# PhotonHome.net
KiCad netlist of a schematic drawn in EAGLE
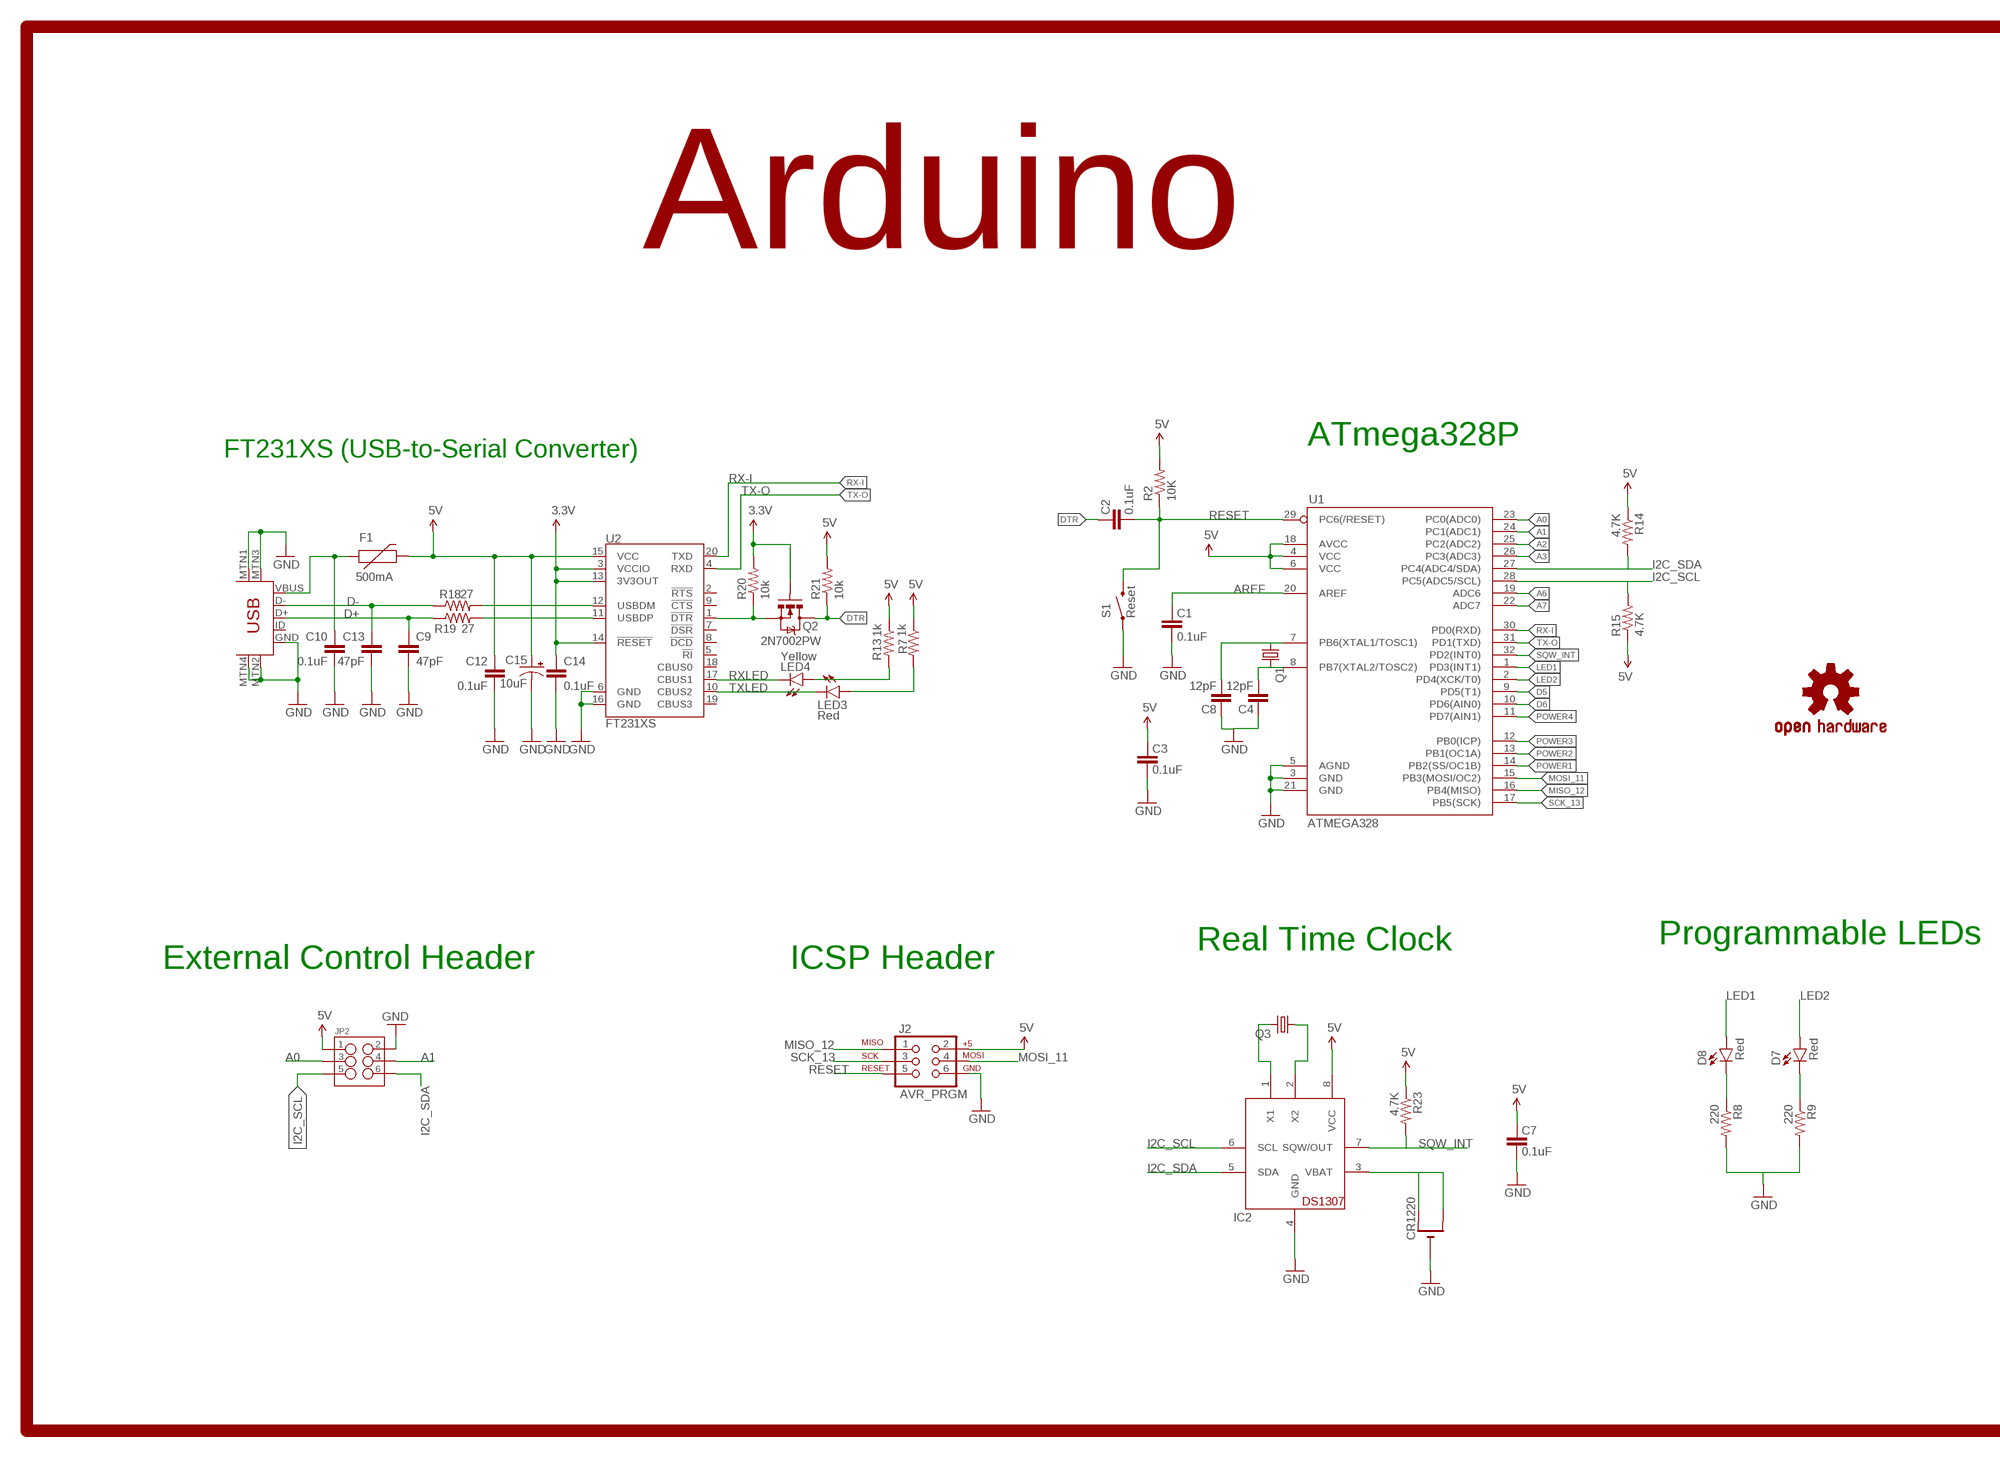
[diagram p0: schematic, sheet 1, part 1 of 2]
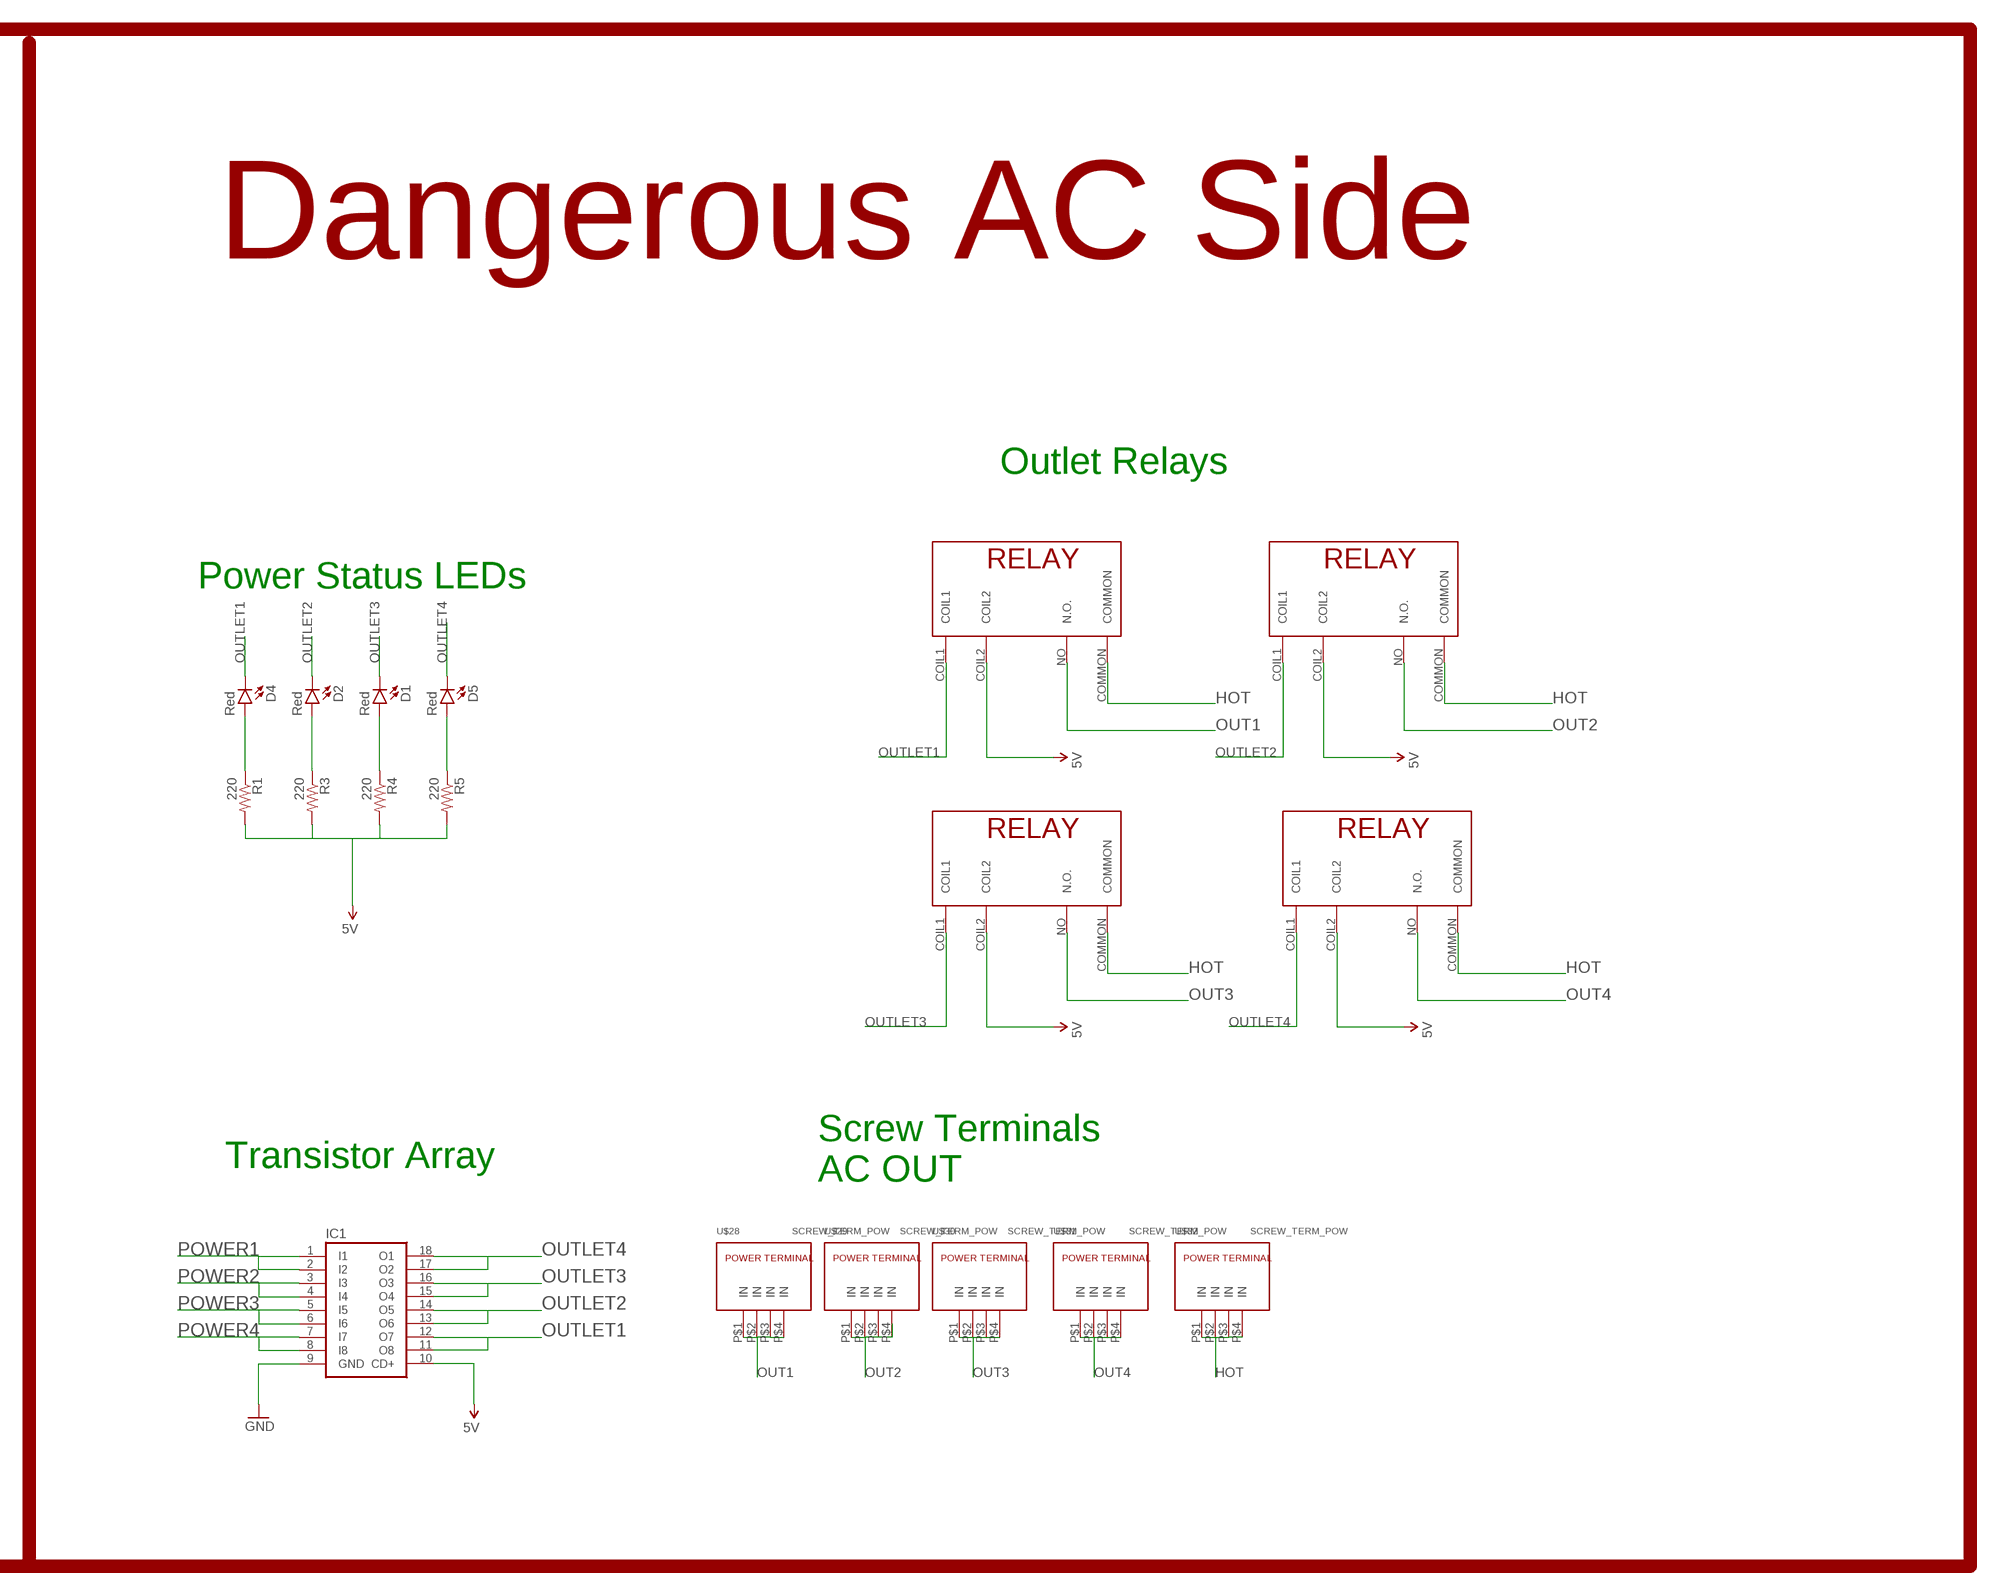
[diagram p1: schematic, sheet 1, part 2 of 2]

(export (version "E")
  (design (tool "Eeschema 10.0.6"))
  (components
    (comp (ref "C1")
      (value "0.1uF")
      (footprint "eagle-import:0805-CAP")
      (libsource (lib "eagle-import") (part "CAP0805-CAP"))
    )
    (comp (ref "C2")
      (value "0.1uF")
      (footprint "eagle-import:0805-CAP")
      (libsource (lib "eagle-import") (part "CAP0805-CAP"))
    )
    (comp (ref "C3")
      (value "0.1uF")
      (footprint "eagle-import:0805-CAP")
      (libsource (lib "eagle-import") (part "CAP0805-CAP"))
    )
    (comp (ref "C4")
      (value "12pF")
      (footprint "eagle-import:0805-CAP")
      (libsource (lib "eagle-import") (part "CAP0805-CAP"))
    )
    (comp (ref "C7")
      (value "0.1uF")
      (footprint "eagle-import:0805-CAP")
      (libsource (lib "eagle-import") (part "CAP0805-CAP"))
    )
    (comp (ref "C8")
      (value "12pF")
      (footprint "eagle-import:0805-CAP")
      (libsource (lib "eagle-import") (part "CAP0805-CAP"))
    )
    (comp (ref "C9")
      (value "47pF")
      (footprint "eagle-import:0805-CAP")
      (libsource (lib "eagle-import") (part "CAP0805-CAP"))
    )
    (comp (ref "C10")
      (value "0.1uF")
      (footprint "eagle-import:0805-CAP")
      (libsource (lib "eagle-import") (part "CAP0805-CAP"))
    )
    (comp (ref "C12")
      (value "0.1uF")
      (footprint "eagle-import:0805-CAP")
      (libsource (lib "eagle-import") (part "CAP0805-CAP"))
    )
    (comp (ref "C13")
      (value "47pF")
      (footprint "eagle-import:0805-CAP")
      (libsource (lib "eagle-import") (part "CAP0805-CAP"))
    )
    (comp (ref "C14")
      (value "0.1uF")
      (footprint "eagle-import:0805-CAP")
      (libsource (lib "eagle-import") (part "CAP0805-CAP"))
    )
    (comp (ref "C15")
      (value "10uF")
      (footprint "eagle-import:EIA3216")
      (libsource (lib "eagle-import") (part "CAP_POL1206"))
    )
    (comp (ref "CR1220")
      (value "CR1220THM")
      (footprint "eagle-import:CR1220-THM")
      (libsource (lib "eagle-import") (part "CR1220THM"))
    )
    (comp (ref "D1")
      (value "Red")
      (footprint "eagle-import:0805-LED")
      (libsource (lib "eagle-import") (part "LED-RED0805"))
    )
    (comp (ref "D2")
      (value "Red")
      (footprint "eagle-import:0805-LED")
      (libsource (lib "eagle-import") (part "LED-RED0805"))
    )
    (comp (ref "D4")
      (value "Red")
      (footprint "eagle-import:0805-LED")
      (libsource (lib "eagle-import") (part "LED-RED0805"))
    )
    (comp (ref "D5")
      (value "Red")
      (footprint "eagle-import:0805-LED")
      (libsource (lib "eagle-import") (part "LED-RED0805"))
    )
    (comp (ref "D7")
      (value "Red")
      (footprint "eagle-import:0805-LED")
      (libsource (lib "eagle-import") (part "LED-RED0805"))
    )
    (comp (ref "D8")
      (value "Red")
      (footprint "eagle-import:0805-LED")
      (libsource (lib "eagle-import") (part "LED-RED0805"))
    )
    (comp (ref "F1")
      (value "500mA")
      (footprint "eagle-import:PTC-1206")
      (libsource (lib "eagle-import") (part "PTCSMD"))
    )
    (comp (ref "IC1")
      (value "ULN2803ASOIC18-W")
      (footprint "eagle-import:SOIC18-W")
      (libsource (lib "eagle-import") (part "ULN2803ASOIC18-W"))
    )
    (comp (ref "IC2")
      (value "DS1307SO08")
      (footprint "eagle-import:SO08-150MIL")
      (libsource (lib "eagle-import") (part "DS1307SO08"))
    )
    (comp (ref "J2")
      (value "AVR_PRGM")
      (footprint "eagle-import:2X3")
      (libsource (lib "eagle-import") (part "AVR_SPI_PRG_6PTH"))
    )
    (comp (ref "JP2")
      (value "M03X2SHROUD")
      (footprint "eagle-import:2X3-SHROUDED")
      (libsource (lib "eagle-import") (part "M03X2SHROUD"))
    )
    (comp (ref "LED3")
      (value "Red")
      (footprint "eagle-import:0805-LED")
      (libsource (lib "eagle-import") (part "LED-RED0805"))
    )
    (comp (ref "LED4")
      (value "Yellow")
      (footprint "eagle-import:0805-LED")
      (libsource (lib "eagle-import") (part "LED-RED0805"))
    )
    (comp (ref "MINIUSB")
      (value "USB-MINIB-5PIN")
      (footprint "eagle-import:USB-MINIB")
      (libsource (lib "eagle-import") (part "USB-MINIB-5PIN"))
    )
    (comp (ref "Q1")
      (value "CRYSTALHC49UP")
      (footprint "eagle-import:HC49UP")
      (libsource (lib "eagle-import") (part "adafruit_CRYSTALHC49UP"))
    )
    (comp (ref "Q2")
      (value "2N7002PW")
      (footprint "eagle-import:SOT323")
      (libsource (lib "eagle-import") (part "MOSFET-NCHANNEL2N7002PW"))
    )
    (comp (ref "Q3")
      (value "CRYSTALTC38H")
      (footprint "eagle-import:TC38H")
      (libsource (lib "eagle-import") (part "CRYSTALTC38H"))
    )
    (comp (ref "R1")
      (value "220")
      (footprint "eagle-import:0805")
      (libsource (lib "eagle-import") (part "RES0805-RES"))
    )
    (comp (ref "R2")
      (value "10K")
      (footprint "eagle-import:0805")
      (libsource (lib "eagle-import") (part "RES0805-RES"))
    )
    (comp (ref "R3")
      (value "220")
      (footprint "eagle-import:0805")
      (libsource (lib "eagle-import") (part "RES0805-RES"))
    )
    (comp (ref "R4")
      (value "220")
      (footprint "eagle-import:0805")
      (libsource (lib "eagle-import") (part "RES0805-RES"))
    )
    (comp (ref "R5")
      (value "220")
      (footprint "eagle-import:0805")
      (libsource (lib "eagle-import") (part "RES0805-RES"))
    )
    (comp (ref "R7")
      (value "1k")
      (footprint "eagle-import:0805")
      (libsource (lib "eagle-import") (part "RES0805-RES"))
    )
    (comp (ref "R8")
      (value "220")
      (footprint "eagle-import:0805")
      (libsource (lib "eagle-import") (part "RES0805-RES"))
    )
    (comp (ref "R9")
      (value "220")
      (footprint "eagle-import:0805")
      (libsource (lib "eagle-import") (part "RES0805-RES"))
    )
    (comp (ref "R13")
      (value "1k")
      (footprint "eagle-import:0805")
      (libsource (lib "eagle-import") (part "RES0805-RES"))
    )
    (comp (ref "R14")
      (value "4.7K")
      (footprint "eagle-import:0805")
      (libsource (lib "eagle-import") (part "RES0805-RES"))
    )
    (comp (ref "R15")
      (value "4.7K")
      (footprint "eagle-import:0805")
      (libsource (lib "eagle-import") (part "RES0805-RES"))
    )
    (comp (ref "R18")
      (value "27")
      (footprint "eagle-import:0805")
      (libsource (lib "eagle-import") (part "RES0805-RES"))
    )
    (comp (ref "R19")
      (value "27")
      (footprint "eagle-import:0805")
      (libsource (lib "eagle-import") (part "RES0805-RES"))
    )
    (comp (ref "R20")
      (value "10k")
      (footprint "eagle-import:0805")
      (libsource (lib "eagle-import") (part "RES0805-RES"))
    )
    (comp (ref "R21")
      (value "10k")
      (footprint "eagle-import:0805")
      (libsource (lib "eagle-import") (part "RES0805-RES"))
    )
    (comp (ref "R23")
      (value "4.7K")
      (footprint "eagle-import:0805")
      (libsource (lib "eagle-import") (part "RES0805-RES"))
    )
    (comp (ref "RELAY1")
      (value "RELAY_NO")
      (footprint "eagle-import:RELAY_G2RL-1A")
      (libsource (lib "eagle-import") (part "RELAY_NO"))
    )
    (comp (ref "RELAY2")
      (value "RELAY_NO")
      (footprint "eagle-import:RELAY_G2RL-1A")
      (libsource (lib "eagle-import") (part "RELAY_NO"))
    )
    (comp (ref "RELAY3")
      (value "RELAY_NO")
      (footprint "eagle-import:RELAY_G2RL-1A")
      (libsource (lib "eagle-import") (part "RELAY_NO"))
    )
    (comp (ref "RELAY4")
      (value "RELAY_NO")
      (footprint "eagle-import:RELAY_G2RL-1A")
      (libsource (lib "eagle-import") (part "RELAY_NO"))
    )
    (comp (ref "S1")
      (value "Reset")
      (footprint "eagle-import:TACTILE-SWITCH-SMD-ALT01")
      (libsource (lib "eagle-import") (part "SWITCH-MOMENTARY-2SMD-ALT01"))
    )
    (comp (ref "U$3")
      (value "OSHW-LOGOS")
      (footprint "eagle-import:OSHW-LOGO-S")
      (libsource (lib "eagle-import") (part "OSHW-LOGOS"))
    )
    (comp (ref "U$28")
      (value "SCREW_TERM_POW")
      (footprint "eagle-import:SCREW-TERMINAL-POW")
      (libsource (lib "eagle-import") (part "SCREW_TERM_POW"))
    )
    (comp (ref "U$29")
      (value "SCREW_TERM_POW")
      (footprint "eagle-import:SCREW-TERMINAL-POW")
      (libsource (lib "eagle-import") (part "SCREW_TERM_POW"))
    )
    (comp (ref "U$30")
      (value "SCREW_TERM_POW")
      (footprint "eagle-import:SCREW-TERMINAL-POW")
      (libsource (lib "eagle-import") (part "SCREW_TERM_POW"))
    )
    (comp (ref "U$31")
      (value "SCREW_TERM_POW")
      (footprint "eagle-import:SCREW-TERMINAL-POW")
      (libsource (lib "eagle-import") (part "SCREW_TERM_POW"))
    )
    (comp (ref "U$32")
      (value "SCREW_TERM_POW")
      (footprint "eagle-import:SCREW-TERMINAL-POW")
      (libsource (lib "eagle-import") (part "SCREW_TERM_POW"))
    )
    (comp (ref "U1")
      (value "ATMEGA328")
      (footprint "eagle-import:TQFP32-08")
      (libsource (lib "eagle-import") (part "ATMEGA168"))
    )
    (comp (ref "U2")
      (value "FT231XS")
      (footprint "eagle-import:SSOP20_L")
      (libsource (lib "eagle-import") (part "FT231XS"))
    )
  )
  (nets
    (net (code "1") (name "/AREF") (class "Default")
      (node (ref "C1") (pin "2") (pinfunction "2_2") (pintype "passive"))
      (node (ref "U1") (pin "20") (pinfunction "AREF_20") (pintype "bidirectional"))
    )
    (net (code "2") (name "/D+") (class "Default")
      (node (ref "C9") (pin "1") (pinfunction "1_1") (pintype "passive"))
      (node (ref "MINIUSB") (pin "D+") (pinfunction "D+_D+") (pintype "bidirectional"))
      (node (ref "R19") (pin "1") (pinfunction "1_1") (pintype "passive"))
    )
    (net (code "3") (name "/D-") (class "Default")
      (node (ref "C13") (pin "1") (pinfunction "1_1") (pintype "passive"))
      (node (ref "MINIUSB") (pin "D-") (pinfunction "D-_D-") (pintype "bidirectional"))
      (node (ref "R18") (pin "1") (pinfunction "1_1") (pintype "passive"))
    )
    (net (code "4") (name "/HOT") (class "Default")
      (node (ref "RELAY1") (pin "COMMON") (pinfunction "COMMON_COMMON") (pintype "bidirectional"))
      (node (ref "RELAY2") (pin "COMMON") (pinfunction "COMMON_COMMON") (pintype "bidirectional"))
      (node (ref "RELAY3") (pin "COMMON") (pinfunction "COMMON_COMMON") (pintype "bidirectional"))
      (node (ref "RELAY4") (pin "COMMON") (pinfunction "COMMON_COMMON") (pintype "bidirectional"))
      (node (ref "U$32") (pin "P$1") (pinfunction "IN_P$1") (pintype "bidirectional"))
      (node (ref "U$32") (pin "P$2") (pinfunction "IN_P$2") (pintype "bidirectional"))
      (node (ref "U$32") (pin "P$3") (pinfunction "IN_P$3") (pintype "bidirectional"))
      (node (ref "U$32") (pin "P$4") (pinfunction "IN_P$4") (pintype "bidirectional"))
    )
    (net (code "5") (name "/I2C_SDA") (class "Default")
      (node (ref "IC2") (pin "5") (pinfunction "SDA_5") (pintype "bidirectional"))
      (node (ref "JP2") (pin "6") (pinfunction "6_6") (pintype "bidirectional"))
      (node (ref "R14") (pin "2") (pinfunction "2_2") (pintype "passive"))
      (node (ref "U1") (pin "27") (pinfunction "PC4(ADC4/SDA)_27") (pintype "bidirectional"))
    )
    (net (code "6") (name "/OUT1") (class "Default")
      (node (ref "RELAY1") (pin "NO") (pinfunction "N.O._NO") (pintype "bidirectional"))
      (node (ref "U$28") (pin "P$1") (pinfunction "IN_P$1") (pintype "bidirectional"))
      (node (ref "U$28") (pin "P$2") (pinfunction "IN_P$2") (pintype "bidirectional"))
      (node (ref "U$28") (pin "P$3") (pinfunction "IN_P$3") (pintype "bidirectional"))
      (node (ref "U$28") (pin "P$4") (pinfunction "IN_P$4") (pintype "bidirectional"))
    )
    (net (code "7") (name "/OUT2") (class "Default")
      (node (ref "RELAY2") (pin "NO") (pinfunction "N.O._NO") (pintype "bidirectional"))
      (node (ref "U$29") (pin "P$1") (pinfunction "IN_P$1") (pintype "bidirectional"))
      (node (ref "U$29") (pin "P$2") (pinfunction "IN_P$2") (pintype "bidirectional"))
      (node (ref "U$29") (pin "P$3") (pinfunction "IN_P$3") (pintype "bidirectional"))
      (node (ref "U$29") (pin "P$4") (pinfunction "IN_P$4") (pintype "bidirectional"))
    )
    (net (code "8") (name "/OUT3") (class "Default")
      (node (ref "RELAY3") (pin "NO") (pinfunction "N.O._NO") (pintype "bidirectional"))
      (node (ref "U$30") (pin "P$1") (pinfunction "IN_P$1") (pintype "bidirectional"))
      (node (ref "U$30") (pin "P$2") (pinfunction "IN_P$2") (pintype "bidirectional"))
      (node (ref "U$30") (pin "P$3") (pinfunction "IN_P$3") (pintype "bidirectional"))
      (node (ref "U$30") (pin "P$4") (pinfunction "IN_P$4") (pintype "bidirectional"))
    )
    (net (code "9") (name "/OUT4") (class "Default")
      (node (ref "RELAY4") (pin "NO") (pinfunction "N.O._NO") (pintype "bidirectional"))
      (node (ref "U$31") (pin "P$1") (pinfunction "IN_P$1") (pintype "bidirectional"))
      (node (ref "U$31") (pin "P$2") (pinfunction "IN_P$2") (pintype "bidirectional"))
      (node (ref "U$31") (pin "P$3") (pinfunction "IN_P$3") (pintype "bidirectional"))
      (node (ref "U$31") (pin "P$4") (pinfunction "IN_P$4") (pintype "bidirectional"))
    )
    (net (code "10") (name "/OUTLET1") (class "Default")
      (node (ref "D4") (pin "2") (pinfunction "C_2") (pintype "passive"))
      (node (ref "IC1") (pin "11") (pinfunction "O8_11") (pintype "open_collector"))
      (node (ref "IC1") (pin "12") (pinfunction "O7_12") (pintype "open_collector"))
      (node (ref "RELAY1") (pin "COIL1") (pinfunction "COIL1_COIL1") (pintype "bidirectional"))
    )
    (net (code "11") (name "/OUTLET2") (class "Default")
      (node (ref "D2") (pin "2") (pinfunction "C_2") (pintype "passive"))
      (node (ref "IC1") (pin "13") (pinfunction "O6_13") (pintype "open_collector"))
      (node (ref "IC1") (pin "14") (pinfunction "O5_14") (pintype "open_collector"))
      (node (ref "RELAY2") (pin "COIL1") (pinfunction "COIL1_COIL1") (pintype "bidirectional"))
    )
    (net (code "12") (name "/OUTLET3") (class "Default")
      (node (ref "D1") (pin "2") (pinfunction "C_2") (pintype "passive"))
      (node (ref "IC1") (pin "15") (pinfunction "O4_15") (pintype "open_collector"))
      (node (ref "IC1") (pin "16") (pinfunction "O3_16") (pintype "open_collector"))
      (node (ref "RELAY3") (pin "COIL1") (pinfunction "COIL1_COIL1") (pintype "bidirectional"))
    )
    (net (code "13") (name "/OUTLET4") (class "Default")
      (node (ref "D5") (pin "2") (pinfunction "C_2") (pintype "passive"))
      (node (ref "IC1") (pin "17") (pinfunction "O2_17") (pintype "open_collector"))
      (node (ref "IC1") (pin "18") (pinfunction "O1_18") (pintype "open_collector"))
      (node (ref "RELAY4") (pin "COIL1") (pinfunction "COIL1_COIL1") (pintype "bidirectional"))
    )
    (net (code "14") (name "/RESET") (class "Default")
      (node (ref "C2") (pin "1") (pinfunction "1_1") (pintype "passive"))
      (node (ref "J2") (pin "5") (pinfunction "5_5") (pintype "passive"))
      (node (ref "R2") (pin "1") (pinfunction "1_1") (pintype "passive"))
      (node (ref "S1") (pin "3") (pinfunction "2_3") (pintype "passive"))
      (node (ref "S1") (pin "4") (pinfunction "2_4") (pintype "passive"))
      (node (ref "U1") (pin "29") (pinfunction "PC6(/RESET)_29") (pintype "bidirectional"))
    )
    (net (code "15") (name "/RXLED") (class "Default")
      (node (ref "LED4") (pin "2") (pinfunction "C_2") (pintype "passive"))
      (node (ref "U2") (pin "17") (pinfunction "CBUS1_17") (pintype "bidirectional"))
    )
    (net (code "16") (name "/TXLED") (class "Default")
      (node (ref "LED3") (pin "2") (pinfunction "C_2") (pintype "passive"))
      (node (ref "U2") (pin "10") (pinfunction "CBUS2_10") (pintype "bidirectional"))
    )
    (net (code "17") (name "3.3V") (class "Default")
      (node (ref "C14") (pin "1") (pinfunction "1_1") (pintype "passive"))
      (node (ref "Q2") (pin "1") (pinfunction "G_1") (pintype "passive"))
      (node (ref "R20") (pin "2") (pinfunction "2_2") (pintype "passive"))
      (node (ref "U2") (pin "13") (pinfunction "3V3OUT_13") (pintype "bidirectional"))
      (node (ref "U2") (pin "14") (pinfunction "~{RESET}_14") (pintype "bidirectional"))
      (node (ref "U2") (pin "3") (pinfunction "VCCIO_3") (pintype "bidirectional"))
    )
    (net (code "18") (name "5V") (class "Default")
      (node (ref "C12") (pin "1") (pinfunction "1_1") (pintype "passive"))
      (node (ref "C15") (pin "A") (pinfunction "+_A") (pintype "passive"))
      (node (ref "C3") (pin "2") (pinfunction "2_2") (pintype "passive"))
      (node (ref "C7") (pin "2") (pinfunction "2_2") (pintype "passive"))
      (node (ref "F1") (pin "2") (pinfunction "2_2") (pintype "bidirectional"))
      (node (ref "IC1") (pin "10") (pinfunction "CD+_10") (pintype "passive"))
      (node (ref "IC2") (pin "8") (pinfunction "VCC_8") (pintype "power_in"))
      (node (ref "J2") (pin "2") (pinfunction "2_2") (pintype "passive"))
      (node (ref "JP2") (pin "1") (pinfunction "1_1") (pintype "bidirectional"))
      (node (ref "R1") (pin "2") (pinfunction "2_2") (pintype "passive"))
      (node (ref "R13") (pin "1") (pinfunction "1_1") (pintype "passive"))
      (node (ref "R14") (pin "1") (pinfunction "1_1") (pintype "passive"))
      (node (ref "R15") (pin "1") (pinfunction "1_1") (pintype "passive"))
      (node (ref "R2") (pin "2") (pinfunction "2_2") (pintype "passive"))
      (node (ref "R21") (pin "2") (pinfunction "2_2") (pintype "passive"))
      (node (ref "R23") (pin "1") (pinfunction "1_1") (pintype "passive"))
      (node (ref "R3") (pin "2") (pinfunction "2_2") (pintype "passive"))
      (node (ref "R4") (pin "2") (pinfunction "2_2") (pintype "passive"))
      (node (ref "R5") (pin "2") (pinfunction "2_2") (pintype "passive"))
      (node (ref "R7") (pin "1") (pinfunction "1_1") (pintype "passive"))
      (node (ref "RELAY1") (pin "COIL2") (pinfunction "COIL2_COIL2") (pintype "bidirectional"))
      (node (ref "RELAY2") (pin "COIL2") (pinfunction "COIL2_COIL2") (pintype "bidirectional"))
      (node (ref "RELAY3") (pin "COIL2") (pinfunction "COIL2_COIL2") (pintype "bidirectional"))
      (node (ref "RELAY4") (pin "COIL2") (pinfunction "COIL2_COIL2") (pintype "bidirectional"))
      (node (ref "U1") (pin "18") (pinfunction "AVCC_18") (pintype "bidirectional"))
      (node (ref "U1") (pin "4") (pinfunction "VCC_4") (pintype "bidirectional"))
      (node (ref "U1") (pin "6") (pinfunction "VCC_6") (pintype "bidirectional"))
      (node (ref "U2") (pin "15") (pinfunction "VCC_15") (pintype "bidirectional"))
    )
    (net (code "19") (name "A0") (class "Default")
      (node (ref "JP2") (pin "3") (pinfunction "3_3") (pintype "bidirectional"))
      (node (ref "U1") (pin "23") (pinfunction "PC0(ADC0)_23") (pintype "bidirectional"))
    )
    (net (code "20") (name "A1") (class "Default")
      (node (ref "JP2") (pin "4") (pinfunction "4_4") (pintype "bidirectional"))
      (node (ref "U1") (pin "24") (pinfunction "PC1(ADC1)_24") (pintype "bidirectional"))
    )
    (net (code "21") (name "A2") (class "Default")
      (node (ref "U1") (pin "25") (pinfunction "PC2(ADC2)_25") (pintype "bidirectional"))
    )
    (net (code "22") (name "A3") (class "Default")
      (node (ref "U1") (pin "26") (pinfunction "PC3(ADC3)_26") (pintype "bidirectional"))
    )
    (net (code "23") (name "A6") (class "Default")
      (node (ref "U1") (pin "19") (pinfunction "ADC6_19") (pintype "bidirectional"))
    )
    (net (code "24") (name "A7") (class "Default")
      (node (ref "U1") (pin "22") (pinfunction "ADC7_22") (pintype "bidirectional"))
    )
    (net (code "25") (name "D5") (class "Default")
      (node (ref "U1") (pin "9") (pinfunction "PD5(T1)_9") (pintype "bidirectional"))
    )
    (net (code "26") (name "D6") (class "Default")
      (node (ref "U1") (pin "10") (pinfunction "PD6(AIN0)_10") (pintype "bidirectional"))
    )
    (net (code "27") (name "DTR") (class "Default")
      (node (ref "C2") (pin "2") (pinfunction "2_2") (pintype "passive"))
      (node (ref "Q2") (pin "3") (pinfunction "D_3") (pintype "passive"))
      (node (ref "R21") (pin "1") (pinfunction "1_1") (pintype "passive"))
    )
    (net (code "28") (name "GND") (class "Default")
      (node (ref "C1") (pin "1") (pinfunction "1_1") (pintype "passive"))
      (node (ref "C10") (pin "2") (pinfunction "2_2") (pintype "passive"))
      (node (ref "C12") (pin "2") (pinfunction "2_2") (pintype "passive"))
      (node (ref "C13") (pin "2") (pinfunction "2_2") (pintype "passive"))
      (node (ref "C14") (pin "2") (pinfunction "2_2") (pintype "passive"))
      (node (ref "C15") (pin "C") (pinfunction "-_C") (pintype "passive"))
      (node (ref "C3") (pin "1") (pinfunction "1_1") (pintype "passive"))
      (node (ref "C4") (pin "2") (pinfunction "2_2") (pintype "passive"))
      (node (ref "C7") (pin "1") (pinfunction "1_1") (pintype "passive"))
      (node (ref "C8") (pin "2") (pinfunction "2_2") (pintype "passive"))
      (node (ref "C9") (pin "2") (pinfunction "2_2") (pintype "passive"))
      (node (ref "CR1220") (pin "-") (pinfunction "-_-") (pintype "passive"))
      (node (ref "IC1") (pin "9") (pinfunction "GND_9") (pintype "power_in"))
      (node (ref "IC2") (pin "4") (pinfunction "GND_4") (pintype "power_in"))
      (node (ref "J2") (pin "6") (pinfunction "6_6") (pintype "passive"))
      (node (ref "JP2") (pin "2") (pinfunction "2_2") (pintype "bidirectional"))
      (node (ref "MINIUSB") (pin "GND") (pinfunction "GND_GND") (pintype "bidirectional"))
      (node (ref "MINIUSB") (pin "MTN1") (pinfunction "MTN2_MTN1") (pintype "bidirectional"))
      (node (ref "MINIUSB") (pin "MTN2") (pinfunction "MTN3_MTN2") (pintype "bidirectional"))
      (node (ref "MINIUSB") (pin "MTN3") (pinfunction "MTN1_MTN3") (pintype "bidirectional"))
      (node (ref "MINIUSB") (pin "MTN4") (pinfunction "MTN4_MTN4") (pintype "bidirectional"))
      (node (ref "R8") (pin "2") (pinfunction "2_2") (pintype "passive"))
      (node (ref "R9") (pin "2") (pinfunction "2_2") (pintype "passive"))
      (node (ref "S1") (pin "1") (pinfunction "1_1") (pintype "passive"))
      (node (ref "S1") (pin "2") (pinfunction "1_2") (pintype "passive"))
      (node (ref "U1") (pin "21") (pinfunction "GND_21") (pintype "bidirectional"))
      (node (ref "U1") (pin "3") (pinfunction "GND_3") (pintype "bidirectional"))
      (node (ref "U1") (pin "5") (pinfunction "AGND_5") (pintype "bidirectional"))
      (node (ref "U2") (pin "16") (pinfunction "GND_16") (pintype "bidirectional"))
      (node (ref "U2") (pin "6") (pinfunction "GND_6") (pintype "bidirectional"))
    )
    (net (code "29") (name "I2C_SCL") (class "Default")
      (node (ref "IC2") (pin "6") (pinfunction "SCL_6") (pintype "bidirectional"))
      (node (ref "JP2") (pin "5") (pinfunction "5_5") (pintype "bidirectional"))
      (node (ref "R15") (pin "2") (pinfunction "2_2") (pintype "passive"))
      (node (ref "U1") (pin "28") (pinfunction "PC5(ADC5/SCL)_28") (pintype "bidirectional"))
    )
    (net (code "30") (name "LED1") (class "Default")
      (node (ref "D8") (pin "1") (pinfunction "A_1") (pintype "passive"))
      (node (ref "U1") (pin "1") (pinfunction "PD3(INT1)_1") (pintype "bidirectional"))
    )
    (net (code "31") (name "LED2") (class "Default")
      (node (ref "D7") (pin "1") (pinfunction "A_1") (pintype "passive"))
      (node (ref "U1") (pin "2") (pinfunction "PD4(XCK/T0)_2") (pintype "bidirectional"))
    )
    (net (code "32") (name "MISO_12") (class "Default")
      (node (ref "J2") (pin "1") (pinfunction "1_1") (pintype "passive"))
      (node (ref "U1") (pin "16") (pinfunction "PB4(MISO)_16") (pintype "bidirectional"))
    )
    (net (code "33") (name "MOSI_11") (class "Default")
      (node (ref "J2") (pin "4") (pinfunction "4_4") (pintype "passive"))
      (node (ref "U1") (pin "15") (pinfunction "PB3(MOSI/OC2)_15") (pintype "bidirectional"))
    )
    (net (code "34") (name "Net-(C10-Pad1)") (class "Default")
      (node (ref "C10") (pin "1") (pinfunction "1_1") (pintype "passive"))
      (node (ref "F1") (pin "1") (pinfunction "1_1") (pintype "bidirectional"))
      (node (ref "MINIUSB") (pin "VBUS") (pinfunction "VBUS_VBUS") (pintype "bidirectional"))
    )
    (net (code "35") (name "Net-(CR1220-+)") (class "Default")
      (node (ref "CR1220") (pin "+1") (pinfunction "+_+1") (pintype "passive"))
      (node (ref "CR1220") (pin "+2") (pinfunction "+1_+2") (pintype "passive"))
      (node (ref "IC2") (pin "3") (pinfunction "VBAT_3") (pintype "power_in"))
    )
    (net (code "36") (name "Net-(D1-A)") (class "Default")
      (node (ref "D1") (pin "1") (pinfunction "A_1") (pintype "passive"))
      (node (ref "R4") (pin "1") (pinfunction "1_1") (pintype "passive"))
    )
    (net (code "37") (name "Net-(D2-A)") (class "Default")
      (node (ref "D2") (pin "1") (pinfunction "A_1") (pintype "passive"))
      (node (ref "R3") (pin "1") (pinfunction "1_1") (pintype "passive"))
    )
    (net (code "38") (name "Net-(D4-A)") (class "Default")
      (node (ref "D4") (pin "1") (pinfunction "A_1") (pintype "passive"))
      (node (ref "R1") (pin "1") (pinfunction "1_1") (pintype "passive"))
    )
    (net (code "39") (name "Net-(D5-A)") (class "Default")
      (node (ref "D5") (pin "1") (pinfunction "A_1") (pintype "passive"))
      (node (ref "R5") (pin "1") (pinfunction "1_1") (pintype "passive"))
    )
    (net (code "40") (name "Net-(D7-C)") (class "Default")
      (node (ref "D7") (pin "2") (pinfunction "C_2") (pintype "passive"))
      (node (ref "R9") (pin "1") (pinfunction "1_1") (pintype "passive"))
    )
    (net (code "41") (name "Net-(D8-C)") (class "Default")
      (node (ref "D8") (pin "2") (pinfunction "C_2") (pintype "passive"))
      (node (ref "R8") (pin "1") (pinfunction "1_1") (pintype "passive"))
    )
    (net (code "42") (name "Net-(IC2-X1)") (class "Default")
      (node (ref "IC2") (pin "1") (pinfunction "X1_1") (pintype "passive"))
      (node (ref "Q3") (pin "2") (pinfunction "2_2") (pintype "passive"))
    )
    (net (code "43") (name "Net-(IC2-X2)") (class "Default")
      (node (ref "IC2") (pin "2") (pinfunction "X2_2") (pintype "passive"))
      (node (ref "Q3") (pin "1") (pinfunction "1_1") (pintype "passive"))
    )
    (net (code "44") (name "Net-(LED3-A)") (class "Default")
      (node (ref "LED3") (pin "1") (pinfunction "A_1") (pintype "passive"))
      (node (ref "R7") (pin "2") (pinfunction "2_2") (pintype "passive"))
    )
    (net (code "45") (name "Net-(LED4-A)") (class "Default")
      (node (ref "LED4") (pin "1") (pinfunction "A_1") (pintype "passive"))
      (node (ref "R13") (pin "2") (pinfunction "2_2") (pintype "passive"))
    )
    (net (code "46") (name "Net-(Q2-S)") (class "Default")
      (node (ref "Q2") (pin "2") (pinfunction "S_2") (pintype "passive"))
      (node (ref "R20") (pin "1") (pinfunction "1_1") (pintype "passive"))
      (node (ref "U2") (pin "1") (pinfunction "~{DTR}_1") (pintype "bidirectional"))
    )
    (net (code "47") (name "Net-(U1-PB6(XTAL1{slash}TOSC1))") (class "Default")
      (node (ref "C8") (pin "1") (pinfunction "1_1") (pintype "passive"))
      (node (ref "Q1") (pin "1") (pinfunction "1_1") (pintype "passive"))
      (node (ref "U1") (pin "7") (pinfunction "PB6(XTAL1/TOSC1)_7") (pintype "bidirectional"))
    )
    (net (code "48") (name "Net-(U1-PB7(XTAL2{slash}TOSC2))") (class "Default")
      (node (ref "C4") (pin "1") (pinfunction "1_1") (pintype "passive"))
      (node (ref "Q1") (pin "2") (pinfunction "2_2") (pintype "passive"))
      (node (ref "U1") (pin "8") (pinfunction "PB7(XTAL2/TOSC2)_8") (pintype "bidirectional"))
    )
    (net (code "49") (name "Net-(U2-USBDM)") (class "Default")
      (node (ref "R18") (pin "2") (pinfunction "2_2") (pintype "passive"))
      (node (ref "U2") (pin "12") (pinfunction "USBDM_12") (pintype "bidirectional"))
    )
    (net (code "50") (name "Net-(U2-USBDP)") (class "Default")
      (node (ref "R19") (pin "2") (pinfunction "2_2") (pintype "passive"))
      (node (ref "U2") (pin "11") (pinfunction "USBDP_11") (pintype "bidirectional"))
    )
    (net (code "51") (name "POWER1") (class "Default")
      (node (ref "IC1") (pin "1") (pinfunction "I1_1") (pintype "input"))
      (node (ref "IC1") (pin "2") (pinfunction "I2_2") (pintype "input"))
      (node (ref "U1") (pin "14") (pinfunction "PB2(SS/OC1B)_14") (pintype "bidirectional"))
    )
    (net (code "52") (name "POWER2") (class "Default")
      (node (ref "IC1") (pin "3") (pinfunction "I3_3") (pintype "input"))
      (node (ref "IC1") (pin "4") (pinfunction "I4_4") (pintype "input"))
      (node (ref "U1") (pin "13") (pinfunction "PB1(OC1A)_13") (pintype "bidirectional"))
    )
    (net (code "53") (name "POWER3") (class "Default")
      (node (ref "IC1") (pin "5") (pinfunction "I5_5") (pintype "input"))
      (node (ref "IC1") (pin "6") (pinfunction "I6_6") (pintype "input"))
      (node (ref "U1") (pin "12") (pinfunction "PB0(ICP)_12") (pintype "bidirectional"))
    )
    (net (code "54") (name "POWER4") (class "Default")
      (node (ref "IC1") (pin "7") (pinfunction "I7_7") (pintype "input"))
      (node (ref "IC1") (pin "8") (pinfunction "I8_8") (pintype "input"))
      (node (ref "U1") (pin "11") (pinfunction "PD7(AIN1)_11") (pintype "bidirectional"))
    )
    (net (code "55") (name "RX-I") (class "Default")
      (node (ref "U1") (pin "30") (pinfunction "PD0(RXD)_30") (pintype "bidirectional"))
      (node (ref "U2") (pin "20") (pinfunction "TXD_20") (pintype "bidirectional"))
    )
    (net (code "56") (name "SCK_13") (class "Default")
      (node (ref "J2") (pin "3") (pinfunction "3_3") (pintype "passive"))
      (node (ref "U1") (pin "17") (pinfunction "PB5(SCK)_17") (pintype "bidirectional"))
    )
    (net (code "57") (name "SQW_INT") (class "Default")
      (node (ref "IC2") (pin "7") (pinfunction "SQW/OUT_7") (pintype "bidirectional"))
      (node (ref "R23") (pin "2") (pinfunction "2_2") (pintype "passive"))
      (node (ref "U1") (pin "32") (pinfunction "PD2(INT0)_32") (pintype "bidirectional"))
    )
    (net (code "58") (name "TX-O") (class "Default")
      (node (ref "U1") (pin "31") (pinfunction "PD1(TXD)_31") (pintype "bidirectional"))
      (node (ref "U2") (pin "4") (pinfunction "RXD_4") (pintype "bidirectional"))
    )
    (net (code "59") (name "unconnected-(MINIUSB-PadID)") (class "Default")
      (node (ref "MINIUSB") (pin "ID") (pinfunction "ID_ID") (pintype "bidirectional"))
    )
    (net (code "60") (name "unconnected-(U2-CBUS0-Pad18)") (class "Default")
      (node (ref "U2") (pin "18") (pinfunction "CBUS0_18") (pintype "bidirectional"))
    )
    (net (code "61") (name "unconnected-(U2-CBUS3-Pad19)") (class "Default")
      (node (ref "U2") (pin "19") (pinfunction "CBUS3_19") (pintype "bidirectional"))
    )
    (net (code "62") (name "unconnected-(U2-~{CTS}-Pad9)") (class "Default")
      (node (ref "U2") (pin "9") (pinfunction "~{CTS}_9") (pintype "bidirectional"))
    )
    (net (code "63") (name "unconnected-(U2-~{DCD}-Pad8)") (class "Default")
      (node (ref "U2") (pin "8") (pinfunction "~{DCD}_8") (pintype "bidirectional"))
    )
    (net (code "64") (name "unconnected-(U2-~{DSR}-Pad7)") (class "Default")
      (node (ref "U2") (pin "7") (pinfunction "~{DSR}_7") (pintype "bidirectional"))
    )
    (net (code "65") (name "unconnected-(U2-~{RI}-Pad5)") (class "Default")
      (node (ref "U2") (pin "5") (pinfunction "~{RI}_5") (pintype "bidirectional"))
    )
    (net (code "66") (name "unconnected-(U2-~{RTS}-Pad2)") (class "Default")
      (node (ref "U2") (pin "2") (pinfunction "~{RTS}_2") (pintype "bidirectional"))
    )
  )
)
